# Receivers.net
KiCad netlist of a schematic drawn in Altium Designer
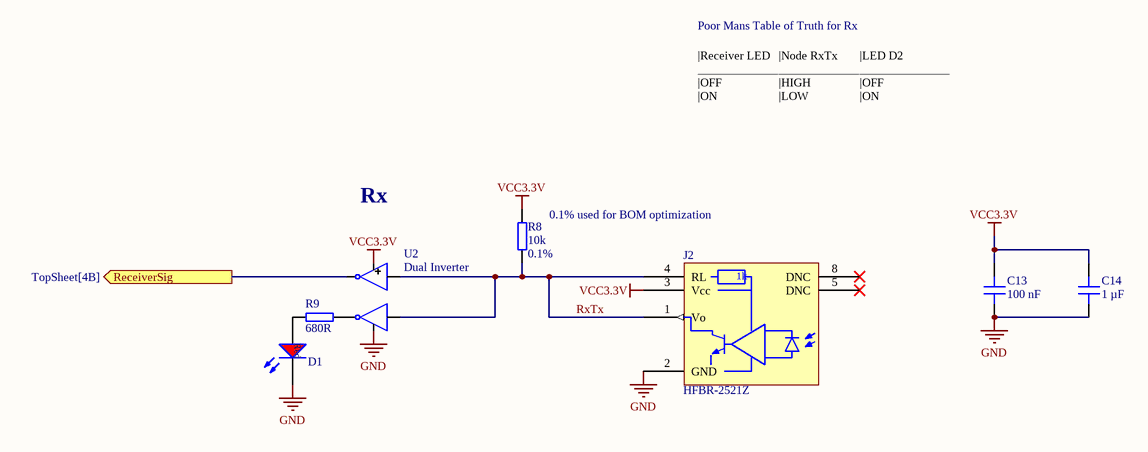
[diagram p0: Receivers.SchDoc]

(export (version "E")
  (design (tool "Eeschema 10.0.6"))
  (components
    (comp (ref "C13")
      (value "100 nF")
      (footprint "C_0603")
      (description "Capacitor 0603, 50 VDC, 100nF, X7R")
      (fields
        (field (name "MANUFACTURER PART NUMBER") "C0603C104K5RAC3121")
        (field (name "MANUFACTURER") "KEMET")
        (field (name "CREATED FROM") "DHufnagel")
      )
      (libsource (lib "user") (part "Capacitor"))
    )
    (comp (ref "C14")
      (value "1 µF")
      (footprint "C_0603")
      (description "Capacitor 0603, 25 VDC, 1 µF, X7R")
      (fields
        (field (name "MANUFACTURER PART NUMBER") "C0603C105K3RAC7411")
        (field (name "MANUFACTURER") "KEMET")
        (field (name "CREATED FROM") "MGremer")
      )
      (libsource (lib "user") (part "Capacitor"))
    )
    (comp (ref "D1")
      (value "150060RS75000")
      (footprint "WL-SMCW_0603")
      (description "WL-SMCW SMD Mono-color Chip LED Waterclear, size 0603, Red, 2 V, 140°")
      (fields
        (field (name "MF") "Wuerth Elektronik")
        (field (name "LCSC PART NUMBER") "C2286")
        (field (name "CREATED") "2018_09_06_AGeiger")
      )
      (libsource (lib "UZOhm_Optical") (part "LED_Red_0603"))
    )
    (comp (ref "J2")
      (value "HFBR-2521Z")
      (footprint "HFBRx5XX")
      (description "Fibre Optic Receivers, LINK HORIZ 5MBd RC VR RoHS")
      (fields
        (field (name "MF") "Boadcom/Avago")
        (field (name "MANUFACTURER") "Broadcom")
        (field (name "CREATED") "2019_04_09_Kreppel")
        (field (name "CREATED FROM") "VStarost")
      )
      (libsource (lib "user") (part "HFBR-2528Z"))
    )
    (comp (ref "R8")
      (value "10k")
      (footprint "RES 0603_1608")
      (description "SMD resistor 0.1%, 10ppm")
      (fields
        (field (name "MANUFACTURER PART NUMBER") "ERA-3ARB103V")
        (field (name "MANUFACTURER") "Panasonic")
        (field (name "TOLERANCE") "0.1%")
        (field (name "CREATED FROM") "DHufnagel")
      )
      (libsource (lib "user") (part "Resistor"))
    )
    (comp (ref "R9")
      (value "680R")
      (footprint "R_0603_N")
      (description "SMD Resistor 0603")
      (fields
        (field (name "TOLERANCE") "1%")
        (field (name "VOLTAGE") "75V")
        (field (name "CREATED") "2018_09_06_AGeiger")
      )
      (libsource (lib "UZOhm_Optical") (part "R_0603"))
    )
    (comp (ref "U2")
      (value "Dual Inverter")
      (footprint "SN74LVC2GU04DCKR")
      (description "This dual inverter is designed for 1.65-V to 5.5-V VCC\r\noperation.")
      (fields (field (name "LCSC PART NUMBER") "C116660"))
      (libsource (lib "UZOhm_Optical") (part "SN74LVC2GU04DCKR"))
    )
  )
  (nets
    (net (code "1") (name "/ReceiverSig") (class "Default")
      (node (ref "U2") (pin "6") (pinfunction "OUT2_6") (pintype "passive"))
    )
    (net (code "2") (name "/RxTx") (class "Default")
      (node (ref "J2") (pin "1") (pinfunction "Vo_1") (pintype "output"))
      (node (ref "J2") (pin "4") (pinfunction "RL_4") (pintype "passive"))
      (node (ref "R8") (pin "2") (pinfunction "2_2") (pintype "passive"))
      (node (ref "U2") (pin "1") (pinfunction "IN1_1") (pintype "passive"))
      (node (ref "U2") (pin "3") (pinfunction "IN2_3") (pintype "passive"))
    )
    (net (code "3") (name "GND") (class "Default")
      (node (ref "C13") (pin "2") (pinfunction "2_2") (pintype "passive"))
      (node (ref "C14") (pin "2") (pinfunction "2_2") (pintype "passive"))
      (node (ref "D1") (pin "1") (pinfunction "K_1") (pintype "passive"))
      (node (ref "J2") (pin "2") (pinfunction "GND_2") (pintype "power_in"))
      (node (ref "U2") (pin "2") (pinfunction "GND_2") (pintype "passive"))
    )
    (net (code "4") (name "Net-(D1-A)") (class "Default")
      (node (ref "D1") (pin "2") (pinfunction "A_2") (pintype "passive"))
      (node (ref "R9") (pin "2") (pinfunction "2_2") (pintype "passive"))
    )
    (net (code "5") (name "Net-(R9-Pad1)") (class "Default")
      (node (ref "R9") (pin "1") (pinfunction "1_1") (pintype "passive"))
      (node (ref "U2") (pin "4") (pinfunction "OUT2_4") (pintype "passive"))
    )
    (net (code "6") (name "VCC3.3V") (class "Default")
      (node (ref "C13") (pin "1") (pinfunction "1_1") (pintype "passive"))
      (node (ref "C14") (pin "1") (pinfunction "1_1") (pintype "passive"))
      (node (ref "J2") (pin "3") (pinfunction "Vcc_3") (pintype "power_in"))
      (node (ref "R8") (pin "1") (pinfunction "1_1") (pintype "passive"))
      (node (ref "U2") (pin "5") (pinfunction "VCC_5") (pintype "passive"))
    )
    (net (code "7") (name "unconnected-(J2-DNC-Pad5)") (class "Default")
      (node (ref "J2") (pin "5") (pinfunction "DNC_5") (pintype "passive+no_connect"))
    )
    (net (code "8") (name "unconnected-(J2-DNC-Pad8)") (class "Default")
      (node (ref "J2") (pin "8") (pinfunction "DNC_8") (pintype "passive+no_connect"))
    )
  )
)
